# AX5043_schema.net
KiCad netlist of a schematic drawn in Altium Designer
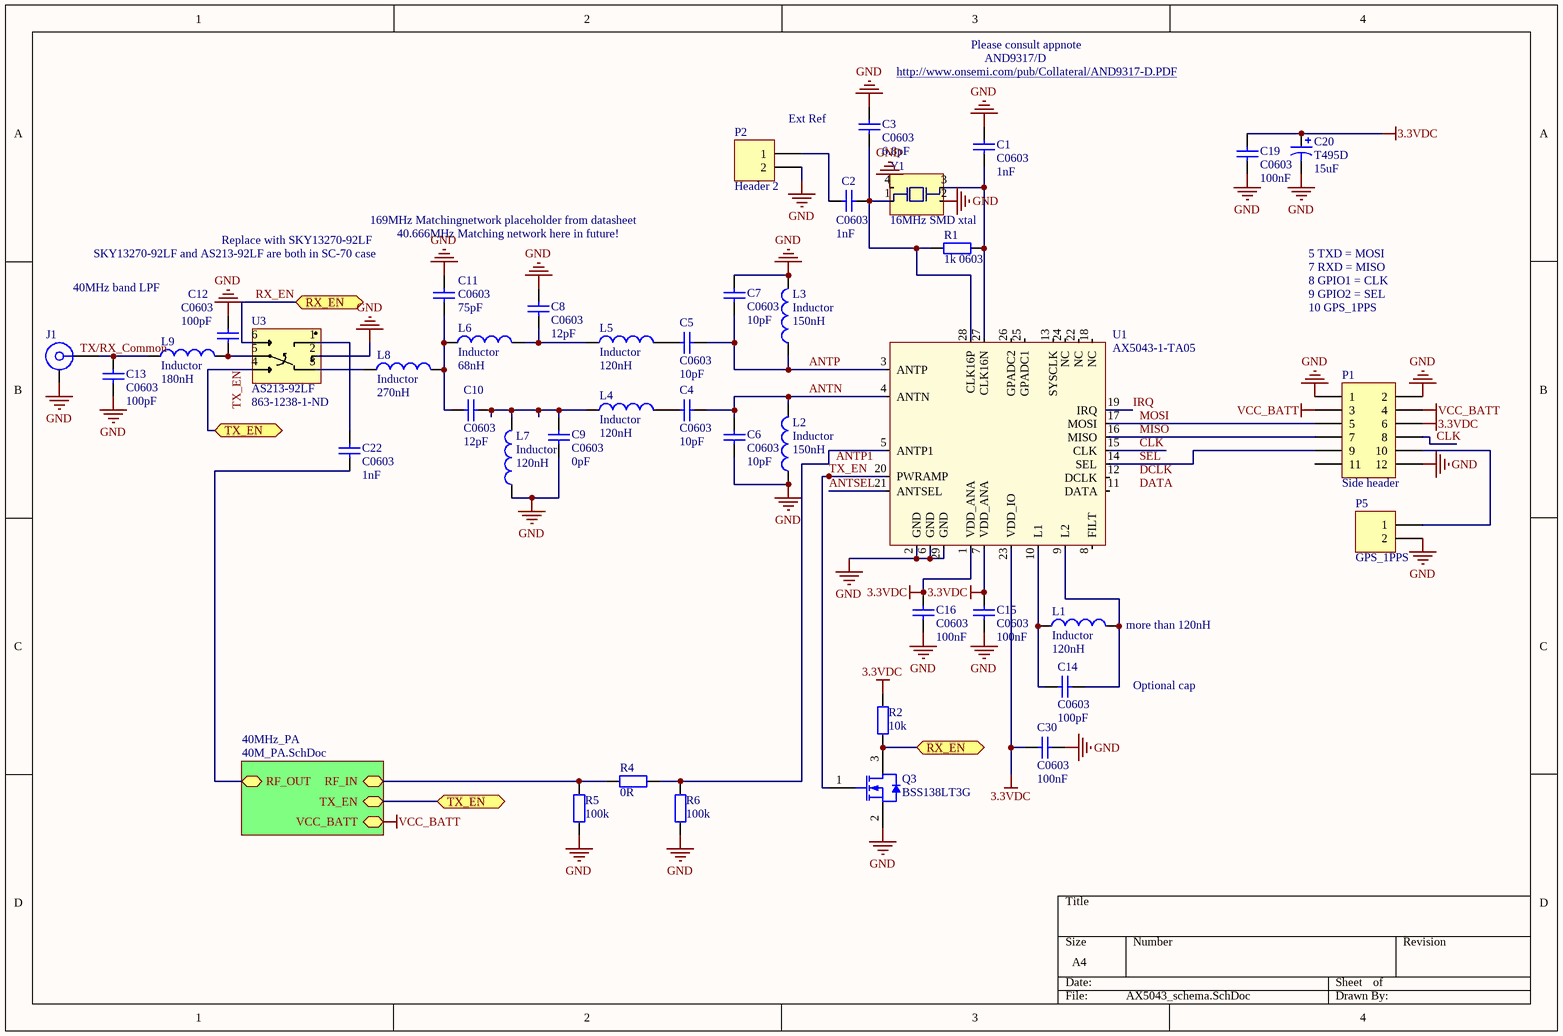
[diagram p0: AX5043_schema.SchDoc]

(export (version "E")
  (design (tool "Eeschema 10.0.6"))
  (components
    (comp (ref "C1")
      (value "C0603")
      (footprint "0603")
      (description "Ceramic Chip Capacitor - Standard")
      (fields (field (name "ALTIUM_VALUE") "1nF") (field (name "PUBLISHER") "Altium Limited"))
      (libsource (lib "KEMET Chip Capacitor") (part "C0603"))
    )
    (comp (ref "C2")
      (value "C0603")
      (footprint "0603")
      (description "Ceramic Chip Capacitor - Standard")
      (fields (field (name "ALTIUM_VALUE") "1nF") (field (name "PUBLISHER") "Altium Limited"))
      (libsource (lib "KEMET Chip Capacitor") (part "C0603"))
    )
    (comp (ref "C3")
      (value "C0603")
      (footprint "0603")
      (description "Ceramic Chip Capacitor - Standard")
      (fields (field (name "ALTIUM_VALUE") "6.8pF") (field (name "PUBLISHER") "Altium Limited"))
      (libsource (lib "KEMET Chip Capacitor") (part "C0603"))
    )
    (comp (ref "C4")
      (value "C0603")
      (footprint "0603")
      (description "Ceramic Chip Capacitor - Standard")
      (fields (field (name "ALTIUM_VALUE") "10pF") (field (name "PUBLISHER") "Altium Limited"))
      (libsource (lib "KEMET Chip Capacitor") (part "C0603"))
    )
    (comp (ref "C5")
      (value "C0603")
      (footprint "0603")
      (description "Ceramic Chip Capacitor - Standard")
      (fields (field (name "ALTIUM_VALUE") "10pF") (field (name "PUBLISHER") "Altium Limited"))
      (libsource (lib "KEMET Chip Capacitor") (part "C0603"))
    )
    (comp (ref "C6")
      (value "C0603")
      (footprint "0603")
      (description "Ceramic Chip Capacitor - Standard")
      (fields (field (name "ALTIUM_VALUE") "10pF") (field (name "PUBLISHER") "Altium Limited"))
      (libsource (lib "KEMET Chip Capacitor") (part "C0603"))
    )
    (comp (ref "C7")
      (value "C0603")
      (footprint "0603")
      (description "Ceramic Chip Capacitor - Standard")
      (fields (field (name "ALTIUM_VALUE") "10pF") (field (name "PUBLISHER") "Altium Limited"))
      (libsource (lib "KEMET Chip Capacitor") (part "C0603"))
    )
    (comp (ref "C8")
      (value "C0603")
      (footprint "0603")
      (description "Ceramic Chip Capacitor - Standard")
      (fields (field (name "ALTIUM_VALUE") "12pF") (field (name "PUBLISHER") "Altium Limited"))
      (libsource (lib "KEMET Chip Capacitor") (part "C0603"))
    )
    (comp (ref "C9")
      (value "C0603")
      (footprint "0603")
      (description "Ceramic Chip Capacitor - Standard")
      (fields (field (name "ALTIUM_VALUE") "0pF") (field (name "PUBLISHER") "Altium Limited"))
      (libsource (lib "KEMET Chip Capacitor") (part "C0603"))
    )
    (comp (ref "C10")
      (value "C0603")
      (footprint "0603")
      (description "Ceramic Chip Capacitor - Standard")
      (fields (field (name "ALTIUM_VALUE") "12pF") (field (name "PUBLISHER") "Altium Limited"))
      (libsource (lib "KEMET Chip Capacitor") (part "C0603"))
    )
    (comp (ref "C11")
      (value "C0603")
      (footprint "0603")
      (description "Ceramic Chip Capacitor - Standard")
      (fields (field (name "ALTIUM_VALUE") "75pF") (field (name "PUBLISHER") "Altium Limited"))
      (libsource (lib "KEMET Chip Capacitor") (part "C0603"))
    )
    (comp (ref "C12")
      (value "C0603")
      (footprint "0603")
      (description "Ceramic Chip Capacitor - Standard")
      (fields (field (name "ALTIUM_VALUE") "100pF") (field (name "PUBLISHER") "Altium Limited"))
      (libsource (lib "KEMET Chip Capacitor") (part "C0603"))
    )
    (comp (ref "C13")
      (value "C0603")
      (footprint "0603")
      (description "Ceramic Chip Capacitor - Standard")
      (fields (field (name "ALTIUM_VALUE") "100pF") (field (name "PUBLISHER") "Altium Limited"))
      (libsource (lib "KEMET Chip Capacitor") (part "C0603"))
    )
    (comp (ref "C14")
      (value "C0603")
      (footprint "0603")
      (description "Ceramic Chip Capacitor - Standard")
      (fields (field (name "ALTIUM_VALUE") "100pF") (field (name "PUBLISHER") "Altium Limited"))
      (libsource (lib "KEMET Chip Capacitor") (part "C0603"))
    )
    (comp (ref "C15")
      (value "C0603")
      (footprint "0603")
      (description "Ceramic Chip Capacitor - Standard")
      (fields (field (name "ALTIUM_VALUE") "100nF") (field (name "PUBLISHER") "Altium Limited"))
      (libsource (lib "KEMET Chip Capacitor") (part "C0603"))
    )
    (comp (ref "C16")
      (value "C0603")
      (footprint "0603")
      (description "Ceramic Chip Capacitor - Standard")
      (fields (field (name "ALTIUM_VALUE") "100nF") (field (name "PUBLISHER") "Altium Limited"))
      (libsource (lib "KEMET Chip Capacitor") (part "C0603"))
    )
    (comp (ref "C19")
      (value "C0603")
      (footprint "0603")
      (description "Ceramic Chip Capacitor - Standard")
      (fields (field (name "ALTIUM_VALUE") "100nF") (field (name "PUBLISHER") "Altium Limited"))
      (libsource (lib "KEMET Chip Capacitor") (part "C0603"))
    )
    (comp (ref "C20")
      (value "T495D")
      (footprint "D")
      (description "Solid Tantalum Chip Capacitor, Standard T495 Series - Low ESR, Surge Robust")
      (fields (field (name "ALTIUM_VALUE") "15uF") (field (name "PUBLISHER") "Altium Limited"))
      (libsource (lib "KEMET Chip Capacitor") (part "T495D"))
    )
    (comp (ref "C22")
      (value "C0603")
      (footprint "0603")
      (description "Ceramic Chip Capacitor - Standard")
      (fields (field (name "ALTIUM_VALUE") "1nF") (field (name "PUBLISHER") "Altium Limited"))
      (libsource (lib "KEMET Chip Capacitor") (part "C0603"))
    )
    (comp (ref "C30")
      (value "C0603")
      (footprint "0603")
      (description "Ceramic Chip Capacitor - Standard")
      (fields (field (name "ALTIUM_VALUE") "100nF") (field (name "PUBLISHER") "Altium Limited"))
      (libsource (lib "KEMET Chip Capacitor") (part "C0603"))
    )
    (comp (ref "J1")
      (value "32K145-400L5")
      (footprint "ROS-32K145-400L5_V")
      (description "SMA Right Angle Jack, Edge Mount, Up to 18 GHz, -55 to 155 degC")
      (libsource (lib "Rosenberger SMA") (part "32K145-400L5"))
    )
    (comp (ref "L1")
      (value "Inductor")
      (footprint "INDC1608L")
      (fields (field (name "ALTIUM_VALUE") "120nH") (field (name "PUBLISHER") "Altium Limited"))
      (libsource (lib "Miscellaneous Devices") (part "Inductor"))
    )
    (comp (ref "L2")
      (value "Inductor")
      (footprint "INDC1608L")
      (fields (field (name "ALTIUM_VALUE") "150nH") (field (name "PUBLISHER") "Altium Limited"))
      (libsource (lib "Miscellaneous Devices") (part "Inductor"))
    )
    (comp (ref "L3")
      (value "Inductor")
      (footprint "INDC1608L")
      (fields (field (name "ALTIUM_VALUE") "150nH") (field (name "PUBLISHER") "Altium Limited"))
      (libsource (lib "Miscellaneous Devices") (part "Inductor"))
    )
    (comp (ref "L4")
      (value "Inductor")
      (footprint "INDC1608L")
      (fields (field (name "ALTIUM_VALUE") "120nH") (field (name "PUBLISHER") "Altium Limited"))
      (libsource (lib "Miscellaneous Devices") (part "Inductor"))
    )
    (comp (ref "L5")
      (value "Inductor")
      (footprint "INDC1608L")
      (fields (field (name "ALTIUM_VALUE") "120nH") (field (name "PUBLISHER") "Altium Limited"))
      (libsource (lib "Miscellaneous Devices") (part "Inductor"))
    )
    (comp (ref "L6")
      (value "Inductor")
      (footprint "INDC1608L")
      (fields (field (name "ALTIUM_VALUE") "68nH") (field (name "PUBLISHER") "Altium Limited"))
      (libsource (lib "Miscellaneous Devices") (part "Inductor"))
    )
    (comp (ref "L7")
      (value "Inductor")
      (footprint "INDC1608L")
      (fields (field (name "ALTIUM_VALUE") "120nH") (field (name "PUBLISHER") "Altium Limited"))
      (libsource (lib "Miscellaneous Devices") (part "Inductor"))
    )
    (comp (ref "L8")
      (value "Inductor")
      (footprint "INDC1608L")
      (fields (field (name "ALTIUM_VALUE") "270nH") (field (name "PUBLISHER") "Altium Limited"))
      (libsource (lib "Miscellaneous Devices") (part "Inductor"))
    )
    (comp (ref "L9")
      (value "Inductor")
      (footprint "INDC1608L")
      (fields (field (name "ALTIUM_VALUE") "180nH") (field (name "PUBLISHER") "Altium Limited"))
      (libsource (lib "Miscellaneous Devices") (part "Inductor"))
    )
    (comp (ref "P1")
      (value "Side header")
      (footprint "HDR2X6H")
      (description "Header, 6-Pin, Dual row, Right Angle")
      (fields (field (name "PUBLISHER") "Altium Limited"))
      (libsource (lib "Miscellaneous Connectors") (part "Header 6X2H"))
    )
    (comp (ref "P2")
      (value "Header 2")
      (footprint "HDR1X2")
      (description "Header, 2-Pin")
      (fields (field (name "PUBLISHER") "Altium Limited"))
      (libsource (lib "Miscellaneous Connectors") (part "Header 2"))
    )
    (comp (ref "P5")
      (value "GPS_1PPS")
      (footprint "HDR1X2")
      (description "Header, 2-Pin")
      (fields (field (name "PUBLISHER") "Altium Limited"))
      (libsource (lib "Miscellaneous Connectors") (part "Header 2"))
    )
    (comp (ref "Q3")
      (value "BSS138LT3G")
      (footprint "ONSC-SOT-23-3-318-08_V")
      (description "Power MOSFET, 200 mA, 50 V, N-Channel, 3-Pin SOT-23, Pb-Free, Tape and Reel")
      (fields (field (name "MANUFACTURER") "On Semiconductor"))
      (libsource (lib "Altium Content Vault") (part "CMP-1058-00765-1"))
    )
    (comp (ref "R1") (value "1k 0603") (footprint "R0603") (libsource (lib "") (part "1k 0603_1")))
    (comp (ref "R2") (value "10k") (footprint "R0603") (libsource (lib "ftg_lib") (part "1k 0603")))
    (comp (ref "R4") (value "0R") (footprint "R0603") (libsource (lib "") (part "1k 0603_2")))
    (comp (ref "R5") (value "100k") (footprint "R0603") (libsource (lib "ftg_lib") (part "1k 0603")))
    (comp (ref "R6") (value "100k") (footprint "R0603") (libsource (lib "ftg_lib") (part "1k 0603")))
    (comp (ref "U1")
      (value "AX5043-1-TA05")
      (footprint "QFN50P500X500X85_HS-29M")
      (description "Data Tranceiver 27-1050MHz Separate TX/RX ports")
      (fields (field (name "MANUFACTURER") "ON Semiconductor"))
      (libsource (lib "ftg_lib") (part "AX5043"))
    )
    (comp (ref "U3")
      (value "AS213-92LF")
      (footprint "SC70_6")
      (description "Switch SPDT 0.1-3GHZ GAAS SC70-6")
      (fields (field (name "SUPPLIER PART NUMBER 1") "863-1238-1-ND"))
      (libsource (lib "ftg_lib") (part "AS213-92LF"))
    )
    (comp (ref "Y1")
      (value "16MHz SMD xtal")
      (footprint "FA-238")
      (description "16MHz SMD xtal 3.20mm x 2.50mm")
      (fields
        (field (name "MANUFACTURER") "Epson")
        (field (name "MANUFACTURER PART NUMBER") "FA-23816.0000MB-C3")
      )
      (libsource (lib "ftg_lib") (part "FA-238_16.0000MB-C3"))
    )
  )
  (nets
    (net (code "1") (name "/ANTN") (class "Default")
      (node (ref "C4") (pin "2") (pinfunction "2_2") (pintype "passive"))
      (node (ref "C6") (pin "2") (pinfunction "2_2") (pintype "passive"))
      (node (ref "L2") (pin "2") (pinfunction "2_2") (pintype "passive"))
      (node (ref "U1") (pin "4") (pinfunction "ANTN_4") (pintype "output"))
    )
    (net (code "2") (name "/ANTP") (class "Default")
      (node (ref "C5") (pin "2") (pinfunction "2_2") (pintype "passive"))
      (node (ref "C7") (pin "1") (pinfunction "1_1") (pintype "passive"))
      (node (ref "L3") (pin "1") (pinfunction "1_1") (pintype "passive"))
      (node (ref "U1") (pin "3") (pinfunction "ANTP_3") (pintype "output"))
    )
    (net (code "4") (name "/ANTSEL") (class "Default")
      (node (ref "U1") (pin "21") (pinfunction "ANTSEL_21") (pintype "output"))
    )
    (net (code "5") (name "/CLK") (class "Default")
      (node (ref "P1") (pin "8") (pinfunction "8_8") (pintype "passive"))
      (node (ref "U1") (pin "15") (pinfunction "CLK_15") (pintype "input"))
    )
    (net (code "8") (name "/IRQ") (class "Default")
      (node (ref "U1") (pin "19") (pinfunction "IRQ_19") (pintype "input"))
    )
    (net (code "9") (name "/MISO") (class "Default")
      (node (ref "P1") (pin "7") (pinfunction "7_7") (pintype "passive"))
      (node (ref "U1") (pin "16") (pinfunction "MISO_16") (pintype "input"))
    )
    (net (code "10") (name "/MOSI") (class "Default")
      (node (ref "P1") (pin "5") (pinfunction "5_5") (pintype "passive"))
      (node (ref "U1") (pin "17") (pinfunction "MOSI_17") (pintype "input"))
    )
    (net (code "11") (name "/RF_IN") (class "Default")
      (node (ref "R4") (pin "2") (pinfunction "2_2") (pintype "passive"))
      (node (ref "R5") (pin "2") (pinfunction "2_2") (pintype "passive"))
    )
    (net (code "12") (name "/RF_OUT") (class "Default")
      (node (ref "C22") (pin "1") (pinfunction "1_1") (pintype "passive"))
    )
    (net (code "13") (name "/RX_EN") (class "Default")
      (node (ref "Q3") (pin "3") (pinfunction "D_3") (pintype "passive"))
      (node (ref "R2") (pin "1") (pinfunction "1_1") (pintype "passive"))
      (node (ref "U3") (pin "6") (pinfunction "6_6") (pintype "passive"))
    )
    (net (code "14") (name "/SEL") (class "Default")
      (node (ref "P1") (pin "9") (pinfunction "9_9") (pintype "passive"))
      (node (ref "U1") (pin "14") (pinfunction "SEL_14") (pintype "input"))
    )
    (net (code "15") (name "/TX_EN") (class "Default")
      (node (ref "Q3") (pin "1") (pinfunction "G_1") (pintype "passive"))
      (node (ref "U1") (pin "20") (pinfunction "PWRAMP_20") (pintype "output"))
      (node (ref "U3") (pin "4") (pinfunction "4_4") (pintype "passive"))
    )
    (net (code "17") (name "3.3VDC") (class "Default")
      (node (ref "C15") (pin "2") (pinfunction "2_2") (pintype "passive"))
      (node (ref "C16") (pin "2") (pinfunction "2_2") (pintype "passive"))
      (node (ref "C19") (pin "2") (pinfunction "2_2") (pintype "passive"))
      (node (ref "C20") (pin "1") (pinfunction "1_1") (pintype "passive"))
      (node (ref "C30") (pin "1") (pinfunction "1_1") (pintype "passive"))
      (node (ref "P1") (pin "6") (pinfunction "6_6") (pintype "passive"))
      (node (ref "R2") (pin "2") (pinfunction "2_2") (pintype "passive"))
      (node (ref "U1") (pin "1") (pinfunction "VDD_ANA_1") (pintype "input"))
      (node (ref "U1") (pin "23") (pinfunction "VDD_IO_23") (pintype "input"))
      (node (ref "U1") (pin "7") (pinfunction "VDD_ANA_7") (pintype "input"))
    )
    (net (code "18") (name "GND") (class "Default")
      (node (ref "C1") (pin "2") (pinfunction "2_2") (pintype "passive"))
      (node (ref "C11") (pin "1") (pinfunction "1_1") (pintype "passive"))
      (node (ref "C12") (pin "1") (pinfunction "1_1") (pintype "passive"))
      (node (ref "C13") (pin "1") (pinfunction "1_1") (pintype "passive"))
      (node (ref "C15") (pin "1") (pinfunction "1_1") (pintype "passive"))
      (node (ref "C16") (pin "1") (pinfunction "1_1") (pintype "passive"))
      (node (ref "C19") (pin "1") (pinfunction "1_1") (pintype "passive"))
      (node (ref "C20") (pin "2") (pinfunction "2_2") (pintype "passive"))
      (node (ref "C3") (pin "2") (pinfunction "2_2") (pintype "passive"))
      (node (ref "C30") (pin "2") (pinfunction "2_2") (pintype "passive"))
      (node (ref "C6") (pin "1") (pinfunction "1_1") (pintype "passive"))
      (node (ref "C7") (pin "2") (pinfunction "2_2") (pintype "passive"))
      (node (ref "C8") (pin "1") (pinfunction "1_1") (pintype "passive"))
      (node (ref "C9") (pin "2") (pinfunction "2_2") (pintype "passive"))
      (node (ref "J1") (pin "MP") (pinfunction "MP_MP") (pintype "passive"))
      (node (ref "L2") (pin "1") (pinfunction "1_1") (pintype "passive"))
      (node (ref "L3") (pin "2") (pinfunction "2_2") (pintype "passive"))
      (node (ref "L7") (pin "1") (pinfunction "1_1") (pintype "passive"))
      (node (ref "P1") (pin "1") (pinfunction "1_1") (pintype "passive"))
      (node (ref "P1") (pin "12") (pinfunction "12_12") (pintype "passive"))
      (node (ref "P1") (pin "2") (pinfunction "2_2") (pintype "passive"))
      (node (ref "P2") (pin "2") (pinfunction "2_2") (pintype "passive"))
      (node (ref "P5") (pin "2") (pinfunction "2_2") (pintype "passive"))
      (node (ref "Q3") (pin "2") (pinfunction "S_2") (pintype "passive"))
      (node (ref "R5") (pin "1") (pinfunction "1_1") (pintype "passive"))
      (node (ref "R6") (pin "1") (pinfunction "1_1") (pintype "passive"))
      (node (ref "U1") (pin "2") (pinfunction "GND_2") (pintype "input"))
      (node (ref "U1") (pin "29") (pinfunction "GND_29") (pintype "input"))
      (node (ref "U1") (pin "6") (pinfunction "GND_6") (pintype "input"))
      (node (ref "U3") (pin "2") (pinfunction "2_2") (pintype "passive"))
      (node (ref "Y1") (pin "2") (pinfunction "2_2") (pintype "passive"))
      (node (ref "Y1") (pin "4") (pinfunction "4_4") (pintype "passive"))
    )
    (net (code "19") (name "Net-(C2-Pad2)") (class "Default")
      (node (ref "C2") (pin "2") (pinfunction "2_2") (pintype "passive"))
      (node (ref "P2") (pin "1") (pinfunction "1_1") (pintype "passive"))
    )
    (net (code "20") (name "Net-(C4-Pad1)") (class "Default")
      (node (ref "C4") (pin "1") (pinfunction "1_1") (pintype "passive"))
      (node (ref "L4") (pin "2") (pinfunction "2_2") (pintype "passive"))
    )
    (net (code "21") (name "Net-(C5-Pad1)") (class "Default")
      (node (ref "C5") (pin "1") (pinfunction "1_1") (pintype "passive"))
      (node (ref "L5") (pin "2") (pinfunction "2_2") (pintype "passive"))
    )
    (net (code "22") (name "Net-(C8-Pad2)") (class "Default")
      (node (ref "C8") (pin "2") (pinfunction "2_2") (pintype "passive"))
      (node (ref "L5") (pin "1") (pinfunction "1_1") (pintype "passive"))
      (node (ref "L6") (pin "2") (pinfunction "2_2") (pintype "passive"))
    )
    (net (code "23") (name "Net-(C10-Pad1)") (class "Default")
      (node (ref "C10") (pin "1") (pinfunction "1_1") (pintype "passive"))
      (node (ref "C11") (pin "2") (pinfunction "2_2") (pintype "passive"))
      (node (ref "L6") (pin "1") (pinfunction "1_1") (pintype "passive"))
      (node (ref "L8") (pin "2") (pinfunction "2_2") (pintype "passive"))
    )
    (net (code "24") (name "Net-(C10-Pad2)") (class "Default")
      (node (ref "C10") (pin "2") (pinfunction "2_2") (pintype "passive"))
      (node (ref "C9") (pin "1") (pinfunction "1_1") (pintype "passive"))
      (node (ref "L4") (pin "1") (pinfunction "1_1") (pintype "passive"))
      (node (ref "L7") (pin "2") (pinfunction "2_2") (pintype "passive"))
    )
    (net (code "25") (name "Net-(C12-Pad2)") (class "Default")
      (node (ref "C12") (pin "2") (pinfunction "2_2") (pintype "passive"))
      (node (ref "L9") (pin "2") (pinfunction "2_2") (pintype "passive"))
      (node (ref "U3") (pin "5") (pinfunction "5_5") (pintype "passive"))
    )
    (net (code "26") (name "Net-(C13-Pad2)") (class "Default")
      (node (ref "C13") (pin "2") (pinfunction "2_2") (pintype "passive"))
      (node (ref "J1") (pin "1") (pinfunction "1_1") (pintype "passive"))
      (node (ref "L9") (pin "1") (pinfunction "1_1") (pintype "passive"))
    )
    (net (code "27") (name "Net-(C22-Pad2)") (class "Default")
      (node (ref "C22") (pin "2") (pinfunction "2_2") (pintype "passive"))
      (node (ref "U3") (pin "1") (pinfunction "1_1") (pintype "passive"))
    )
    (net (code "28") (name "Net-(L8-Pad1)") (class "Default")
      (node (ref "L8") (pin "1") (pinfunction "1_1") (pintype "passive"))
      (node (ref "U3") (pin "3") (pinfunction "3_3") (pintype "passive"))
    )
    (net (code "29") (name "Net-(P1-Pad10)") (class "Default")
      (node (ref "P1") (pin "10") (pinfunction "10_10") (pintype "passive"))
      (node (ref "P5") (pin "1") (pinfunction "1_1") (pintype "passive"))
    )
    (net (code "30") (name "Net-(U1-ANTP1)") (class "Default")
      (node (ref "R4") (pin "1") (pinfunction "1_1") (pintype "passive"))
      (node (ref "R6") (pin "2") (pinfunction "2_2") (pintype "passive"))
      (node (ref "U1") (pin "5") (pinfunction "ANTP1_5") (pintype "output"))
    )
    (net (code "31") (name "Net-(U1-CLK16N)") (class "Default")
      (node (ref "C1") (pin "1") (pinfunction "1_1") (pintype "passive"))
      (node (ref "R1") (pin "2") (pinfunction "2_2") (pintype "passive"))
      (node (ref "U1") (pin "27") (pinfunction "CLK16N_27") (pintype "input"))
      (node (ref "Y1") (pin "3") (pinfunction "3_3") (pintype "passive"))
    )
    (net (code "32") (name "Net-(U1-CLK16P)") (class "Default")
      (node (ref "C2") (pin "1") (pinfunction "1_1") (pintype "passive"))
      (node (ref "C3") (pin "1") (pinfunction "1_1") (pintype "passive"))
      (node (ref "R1") (pin "1") (pinfunction "1_1") (pintype "passive"))
      (node (ref "U1") (pin "28") (pinfunction "CLK16P_28") (pintype "input"))
      (node (ref "Y1") (pin "1") (pinfunction "1_1") (pintype "passive"))
    )
    (net (code "33") (name "Net-(U1-L1)") (class "Default")
      (node (ref "C14") (pin "1") (pinfunction "1_1") (pintype "passive"))
      (node (ref "L1") (pin "1") (pinfunction "1_1") (pintype "passive"))
      (node (ref "U1") (pin "10") (pinfunction "L1_10") (pintype "input"))
    )
    (net (code "34") (name "Net-(U1-L2)") (class "Default")
      (node (ref "C14") (pin "2") (pinfunction "2_2") (pintype "passive"))
      (node (ref "L1") (pin "2") (pinfunction "2_2") (pintype "passive"))
      (node (ref "U1") (pin "9") (pinfunction "L2_9") (pintype "input"))
    )
    (net (code "35") (name "VCC_BATT") (class "Default")
      (node (ref "P1") (pin "3") (pinfunction "3_3") (pintype "passive"))
      (node (ref "P1") (pin "4") (pinfunction "4_4") (pintype "passive"))
    )
    (net (code "36") (name "unconnected-(P1-Pad11)") (class "Default")
      (node (ref "P1") (pin "11") (pinfunction "11_11") (pintype "passive"))
    )
    (net (code "37") (name "unconnected-(U1-DATA-Pad11)") (class "Default")
      (node (ref "U1") (pin "11") (pinfunction "DATA_11") (pintype "input"))
    )
    (net (code "38") (name "unconnected-(U1-DCLK-Pad12)") (class "Default")
      (node (ref "U1") (pin "12") (pinfunction "DCLK_12") (pintype "input"))
    )
    (net (code "39") (name "unconnected-(U1-FILT-Pad8)") (class "Default")
      (node (ref "U1") (pin "8") (pinfunction "FILT_8") (pintype "input"))
    )
    (net (code "40") (name "unconnected-(U1-GPADC1-Pad25)") (class "Default")
      (node (ref "U1") (pin "25") (pinfunction "GPADC1_25") (pintype "input"))
    )
    (net (code "41") (name "unconnected-(U1-GPADC2-Pad26)") (class "Default")
      (node (ref "U1") (pin "26") (pinfunction "GPADC2_26") (pintype "input"))
    )
    (net (code "42") (name "unconnected-(U1-NC-Pad18)") (class "Default")
      (node (ref "U1") (pin "18") (pinfunction "NC_18") (pintype "input"))
    )
    (net (code "43") (name "unconnected-(U1-NC-Pad22)") (class "Default")
      (node (ref "U1") (pin "22") (pinfunction "NC_22") (pintype "input"))
    )
    (net (code "44") (name "unconnected-(U1-NC-Pad24)") (class "Default")
      (node (ref "U1") (pin "24") (pinfunction "NC_24") (pintype "input"))
    )
    (net (code "45") (name "unconnected-(U1-SYSCLK-Pad13)") (class "Default")
      (node (ref "U1") (pin "13") (pinfunction "SYSCLK_13") (pintype "input"))
    )
  )
)
